# vibration.net
KiCad netlist of a schematic drawn in EAGLE
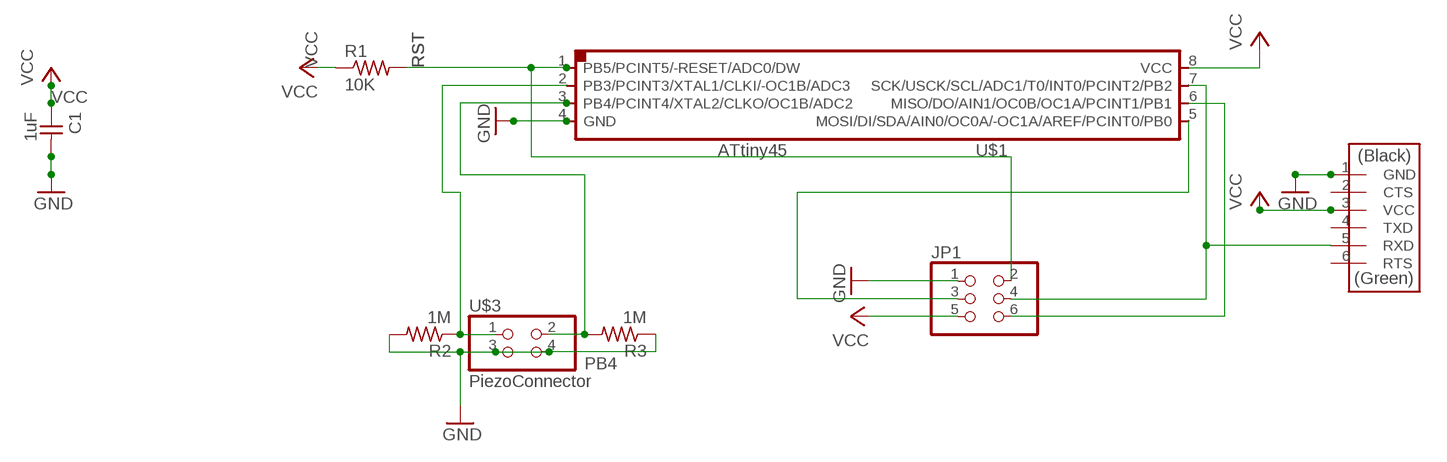
[diagram p0: schematic, sheet 1]

(export (version "E")
  (design (tool "Eeschema 10.0.6"))
  (components
    (comp (ref "C1")
      (value "1uF")
      (footprint "eagle-import:C1206FAB")
      (libsource (lib "eagle-import") (part "CAP-UNPOLARIZEDFAB"))
    )
    (comp (ref "JP1")
      (value "PINHD-2X3-SMD")
      (footprint "eagle-import:2X03SMD")
      (libsource (lib "eagle-import") (part "PINHD-2X3-SMD"))
    )
    (comp (ref "R1")
      (value "10K")
      (footprint "eagle-import:R1206FAB")
      (libsource (lib "eagle-import") (part "RES-US1206FAB"))
    )
    (comp (ref "R2")
      (value "1M")
      (footprint "eagle-import:R1206FAB")
      (libsource (lib "eagle-import") (part "RES-US1206FAB"))
    )
    (comp (ref "R3")
      (value "1M")
      (footprint "eagle-import:R1206FAB")
      (libsource (lib "eagle-import") (part "RES-US1206FAB"))
    )
    (comp (ref "U$1")
      (value "ATTINY45SI")
      (footprint "eagle-import:SOIC8")
      (libsource (lib "eagle-import") (part "ATTINY45SI"))
    )
    (comp (ref "U$2")
      (value "FTDI-SMD-HEADER")
      (footprint "eagle-import:1X06SMD")
      (libsource (lib "eagle-import") (part "FTDI-SMD-HEADER"))
    )
    (comp (ref "U$3")
      (value "PiezoConnector")
      (footprint "eagle-import:2X02SMD")
      (libsource (lib "eagle-import") (part "PINHD-2X2-SMD"))
    )
  )
  (nets
    (net (code "1") (name "/PB4") (class "Default")
      (node (ref "R3") (pin "2") (pinfunction "2_2") (pintype "passive"))
      (node (ref "U$1") (pin "3") (pinfunction "PB4/PCINT4/XTAL2/CLKO/OC1B/ADC2_3") (pintype "bidirectional"))
      (node (ref "U$3") (pin "2") (pinfunction "2_2") (pintype "passive"))
    )
    (net (code "2") (name "/RST") (class "Default")
      (node (ref "JP1") (pin "2") (pinfunction "2_2") (pintype "passive"))
      (node (ref "R1") (pin "2") (pinfunction "2_2") (pintype "passive"))
      (node (ref "U$1") (pin "1") (pinfunction "PB5/PCINT5/-RESET/ADC0/DW_1") (pintype "bidirectional"))
    )
    (net (code "3") (name "GND") (class "Default")
      (node (ref "C1") (pin "2") (pinfunction "2_2") (pintype "passive"))
      (node (ref "JP1") (pin "1") (pinfunction "1_1") (pintype "passive"))
      (node (ref "R2") (pin "2") (pinfunction "2_2") (pintype "passive"))
      (node (ref "R3") (pin "1") (pinfunction "1_1") (pintype "passive"))
      (node (ref "U$1") (pin "4") (pinfunction "GND_4") (pintype "bidirectional"))
      (node (ref "U$2") (pin "1") (pinfunction "GND_1") (pintype "bidirectional"))
      (node (ref "U$3") (pin "3") (pinfunction "3_3") (pintype "passive"))
      (node (ref "U$3") (pin "4") (pinfunction "4_4") (pintype "passive"))
    )
    (net (code "4") (name "Net-(U$1-MISO{slash}DO{slash}AIN1{slash}OC0B{slash}OC1A{slash}PCINT1{slash}PB1)") (class "Default")
      (node (ref "JP1") (pin "6") (pinfunction "6_6") (pintype "passive"))
      (node (ref "U$1") (pin "6") (pinfunction "MISO/DO/AIN1/OC0B/OC1A/PCINT1/PB1_6") (pintype "bidirectional"))
    )
    (net (code "5") (name "Net-(U$1-MOSI{slash}DI{slash}SDA{slash}AIN0{slash}OC0A{slash}-OC1A{slash}AREF{slash}PCINT0{slash}PB0)") (class "Default")
      (node (ref "JP1") (pin "3") (pinfunction "3_3") (pintype "passive"))
      (node (ref "U$1") (pin "5") (pinfunction "MOSI/DI/SDA/AIN0/OC0A/-OC1A/AREF/PCINT0/PB0_5") (pintype "bidirectional"))
    )
    (net (code "6") (name "Net-(U$1-PB3{slash}PCINT3{slash}XTAL1{slash}CLKI{slash}-OC1B{slash}ADC3)") (class "Default")
      (node (ref "R2") (pin "1") (pinfunction "1_1") (pintype "passive"))
      (node (ref "U$1") (pin "2") (pinfunction "PB3/PCINT3/XTAL1/CLKI/-OC1B/ADC3_2") (pintype "bidirectional"))
      (node (ref "U$3") (pin "1") (pinfunction "1_1") (pintype "passive"))
    )
    (net (code "7") (name "Net-(U$1-SCK{slash}USCK{slash}SCL{slash}ADC1{slash}T0{slash}INT0{slash}PCINT2{slash}PB2)") (class "Default")
      (node (ref "JP1") (pin "4") (pinfunction "4_4") (pintype "passive"))
      (node (ref "U$1") (pin "7") (pinfunction "SCK/USCK/SCL/ADC1/T0/INT0/PCINT2/PB2_7") (pintype "bidirectional"))
      (node (ref "U$2") (pin "5") (pinfunction "RXD_5") (pintype "bidirectional"))
    )
    (net (code "8") (name "VCC") (class "Default")
      (node (ref "C1") (pin "1") (pinfunction "1_1") (pintype "passive"))
      (node (ref "JP1") (pin "5") (pinfunction "5_5") (pintype "passive"))
      (node (ref "R1") (pin "1") (pinfunction "1_1") (pintype "passive"))
      (node (ref "U$1") (pin "8") (pinfunction "VCC_8") (pintype "bidirectional"))
      (node (ref "U$2") (pin "3") (pinfunction "VCC_3") (pintype "bidirectional"))
    )
    (net (code "9") (name "unconnected-(U$2-CTS-Pad2)") (class "Default")
      (node (ref "U$2") (pin "2") (pinfunction "CTS_2") (pintype "bidirectional"))
    )
    (net (code "10") (name "unconnected-(U$2-RTS-Pad6)") (class "Default")
      (node (ref "U$2") (pin "6") (pinfunction "RTS_6") (pintype "bidirectional"))
    )
    (net (code "11") (name "unconnected-(U$2-TXD-Pad4)") (class "Default")
      (node (ref "U$2") (pin "4") (pinfunction "TXD_4") (pintype "bidirectional"))
    )
  )
)
